# GRUBswitch_CustomHW_RevB.net
KiCad netlist of a schematic drawn in EAGLE
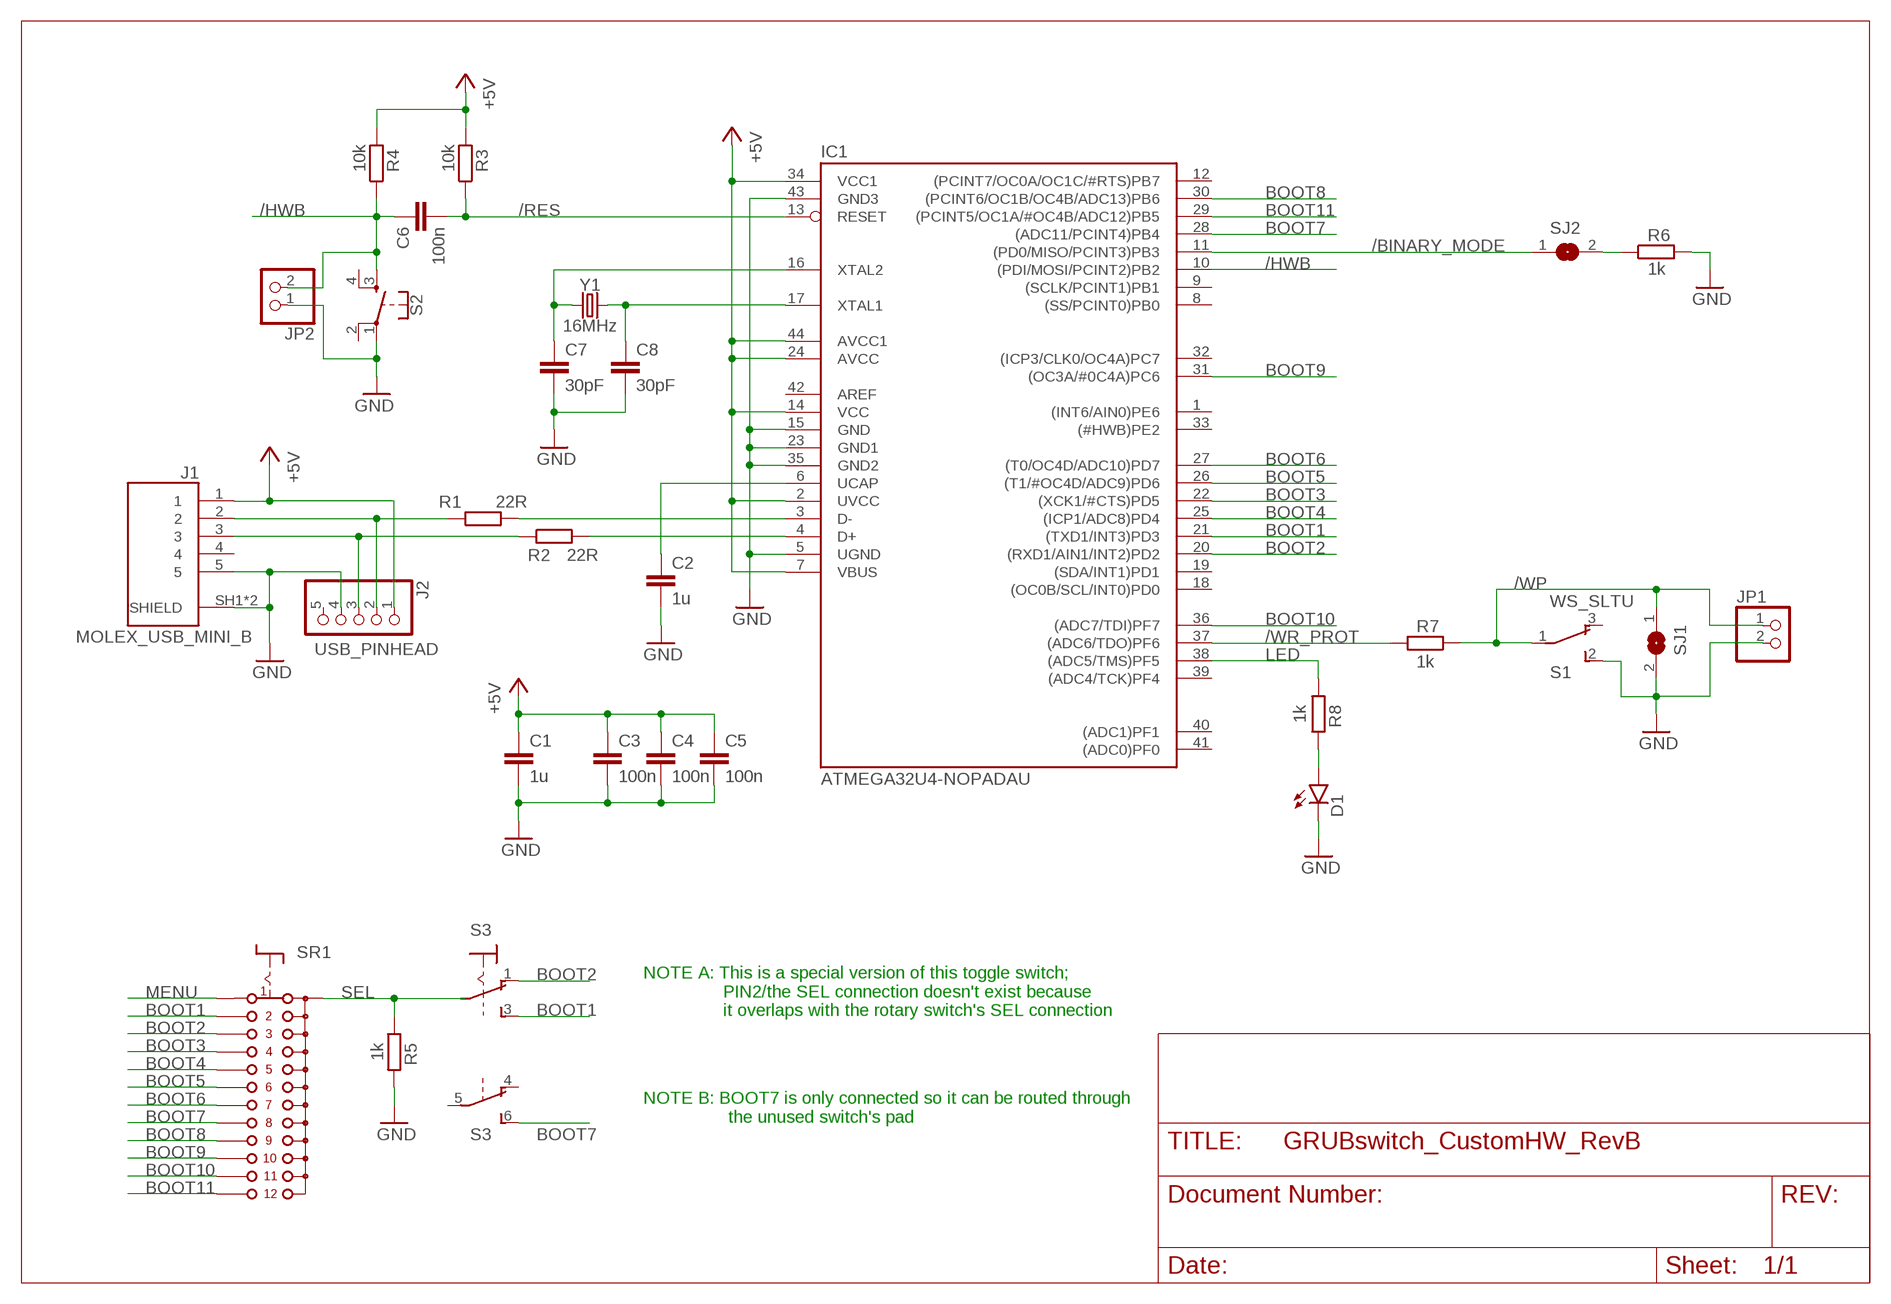
[diagram p0: schematic, sheet 1]

(export (version "E")
  (design (tool "Eeschema 10.0.6"))
  (components
    (comp (ref "C1")
      (value "1u")
      (footprint "eagle-import:C0805")
      (libsource (lib "eagle-import") (part "C-EUC0805"))
    )
    (comp (ref "C2")
      (value "1u")
      (footprint "eagle-import:C0805")
      (libsource (lib "eagle-import") (part "C-EUC0805"))
    )
    (comp (ref "C3")
      (value "100n")
      (footprint "eagle-import:C0805")
      (libsource (lib "eagle-import") (part "C-EUC0805"))
    )
    (comp (ref "C4")
      (value "100n")
      (footprint "eagle-import:C0805")
      (libsource (lib "eagle-import") (part "C-EUC0805"))
    )
    (comp (ref "C5")
      (value "100n")
      (footprint "eagle-import:C0805")
      (libsource (lib "eagle-import") (part "C-EUC0805"))
    )
    (comp (ref "C6")
      (value "100n")
      (footprint "eagle-import:C0805")
      (libsource (lib "eagle-import") (part "C-EUC0805"))
    )
    (comp (ref "C7")
      (value "30pF")
      (footprint "eagle-import:C0805")
      (libsource (lib "eagle-import") (part "C-EUC0805"))
    )
    (comp (ref "C8")
      (value "30pF")
      (footprint "eagle-import:C0805")
      (libsource (lib "eagle-import") (part "C-EUC0805"))
    )
    (comp (ref "D1")
      (value "LEDCHIPLED_0805")
      (footprint "eagle-import:CHIPLED_0805")
      (libsource (lib "eagle-import") (part "LEDCHIPLED_0805"))
    )
    (comp (ref "IC1")
      (value "ATMEGA32U4-NOPADAU")
      (footprint "eagle-import:TQFP44")
      (libsource (lib "eagle-import") (part "ATMEGA32U4-NOPADAU"))
    )
    (comp (ref "J1")
      (value "MOLEX_USB_MINI_B")
      (footprint "eagle-import:MOLEX_502237-0517")
      (libsource (lib "eagle-import") (part "MOLEX_USB_MINI_B"))
    )
    (comp (ref "J2")
      (value "USB_PINHEAD")
      (footprint "eagle-import:1X05")
      (libsource (lib "eagle-import") (part "PINHD-1X5"))
    )
    (comp (ref "JP1")
      (value "PINHD-1X2")
      (footprint "eagle-import:1X02")
      (libsource (lib "eagle-import") (part "PINHD-1X2"))
    )
    (comp (ref "JP2")
      (value "PINHD-1X2")
      (footprint "eagle-import:1X02")
      (libsource (lib "eagle-import") (part "PINHD-1X2"))
    )
    (comp (ref "R1")
      (value "22R")
      (footprint "eagle-import:R0805")
      (libsource (lib "eagle-import") (part "R-EU_R0805"))
    )
    (comp (ref "R2")
      (value "22R")
      (footprint "eagle-import:R0805")
      (libsource (lib "eagle-import") (part "R-EU_R0805"))
    )
    (comp (ref "R3")
      (value "10k")
      (footprint "eagle-import:R0805")
      (libsource (lib "eagle-import") (part "R-EU_R0805"))
    )
    (comp (ref "R4")
      (value "10k")
      (footprint "eagle-import:R0805")
      (libsource (lib "eagle-import") (part "R-EU_R0805"))
    )
    (comp (ref "R5")
      (value "1k")
      (footprint "eagle-import:R0805")
      (libsource (lib "eagle-import") (part "R-EU_R0805"))
    )
    (comp (ref "R6")
      (value "1k")
      (footprint "eagle-import:R0805")
      (libsource (lib "eagle-import") (part "R-EU_R0805"))
    )
    (comp (ref "R7")
      (value "1k")
      (footprint "eagle-import:R0805")
      (libsource (lib "eagle-import") (part "R-EU_R0805"))
    )
    (comp (ref "R8")
      (value "1k")
      (footprint "eagle-import:R0805")
      (libsource (lib "eagle-import") (part "R-EU_R0805"))
    )
    (comp (ref "S1")
      (value "WS_SLTU")
      (footprint "eagle-import:WS_SLTU")
      (libsource (lib "eagle-import") (part "WS_SLTU"))
    )
    (comp (ref "S2")
      (value "MOMENTARY-SWITCH-SPST-2-SMD-4.5MM")
      (footprint "eagle-import:TACTILE_SWITCH_SMD_4.5MM")
      (libsource (lib "eagle-import") (part "MOMENTARY-SWITCH-SPST-2-SMD-4.5MM"))
    )
    (comp (ref "S3")
      (value "M9040P2")
      (footprint "eagle-import:M9040P2")
      (libsource (lib "eagle-import") (part "M9040P2"))
    )
    (comp (ref "SJ1") (value "SJ") (footprint "eagle-import:SJ") (libsource (lib "eagle-import") (part "SJ")))
    (comp (ref "SJ2") (value "SJ") (footprint "eagle-import:SJ") (libsource (lib "eagle-import") (part "SJ")))
    (comp (ref "SR1")
      (value "CK101X12+")
      (footprint "eagle-import:CK101X12+")
      (libsource (lib "eagle-import") (part "CK101X12+"))
    )
    (comp (ref "Y1")
      (value "16MHz")
      (footprint "eagle-import:CRYSTAL-SMD-5X3.2-2PAD")
      (libsource (lib "eagle-import") (part "CRYSTALSMD-5X3.2-2PAD"))
    )
  )
  (nets
    (net (code "1") (name "+5V") (class "Default")
      (node (ref "C1") (pin "1") (pinfunction "1_1") (pintype "passive"))
      (node (ref "C3") (pin "1") (pinfunction "1_1") (pintype "passive"))
      (node (ref "C4") (pin "1") (pinfunction "1_1") (pintype "passive"))
      (node (ref "C5") (pin "1") (pinfunction "1_1") (pintype "passive"))
      (node (ref "IC1") (pin "14") (pinfunction "VCC_14") (pintype "power_in"))
      (node (ref "IC1") (pin "2") (pinfunction "UVCC_2") (pintype "power_in"))
      (node (ref "IC1") (pin "24") (pinfunction "AVCC_24") (pintype "power_in"))
      (node (ref "IC1") (pin "34") (pinfunction "VCC1_34") (pintype "power_in"))
      (node (ref "IC1") (pin "44") (pinfunction "AVCC1_44") (pintype "power_in"))
      (node (ref "IC1") (pin "7") (pinfunction "VBUS_7") (pintype "input"))
      (node (ref "J1") (pin "1") (pinfunction "1_1") (pintype "passive"))
      (node (ref "J2") (pin "1") (pinfunction "1_1") (pintype "passive"))
      (node (ref "R3") (pin "2") (pinfunction "2_2") (pintype "passive"))
      (node (ref "R4") (pin "2") (pinfunction "2_2") (pintype "passive"))
    )
    (net (code "2") (name "/AREF") (class "Default")
      (node (ref "IC1") (pin "42") (pinfunction "AREF_42") (pintype "power_in"))
    )
    (net (code "3") (name "/BOOT1") (class "Default")
      (node (ref "IC1") (pin "21") (pinfunction "(TXD1/INT3)PD3_21") (pintype "bidirectional"))
      (node (ref "S3") (pin "3") (pinfunction "S_3") (pintype "passive"))
      (node (ref "SR1") (pin "2") (pinfunction "2_2") (pintype "passive"))
    )
    (net (code "4") (name "/BOOT2") (class "Default")
      (node (ref "IC1") (pin "20") (pinfunction "(RXD1/AIN1/INT2)PD2_20") (pintype "bidirectional"))
      (node (ref "S3") (pin "1") (pinfunction "O_1") (pintype "passive"))
      (node (ref "SR1") (pin "3") (pinfunction "3_3") (pintype "passive"))
    )
    (net (code "5") (name "/BOOT3") (class "Default")
      (node (ref "IC1") (pin "22") (pinfunction "(XCK1/#CTS)PD5_22") (pintype "bidirectional"))
      (node (ref "SR1") (pin "4") (pinfunction "4_4") (pintype "passive"))
    )
    (net (code "6") (name "/BOOT4") (class "Default")
      (node (ref "IC1") (pin "25") (pinfunction "(ICP1/ADC8)PD4_25") (pintype "bidirectional"))
      (node (ref "SR1") (pin "5") (pinfunction "5_5") (pintype "passive"))
    )
    (net (code "7") (name "/BOOT5") (class "Default")
      (node (ref "IC1") (pin "26") (pinfunction "(T1/#OC4D/ADC9)PD6_26") (pintype "bidirectional"))
      (node (ref "SR1") (pin "6") (pinfunction "6_6") (pintype "passive"))
    )
    (net (code "8") (name "/BOOT6") (class "Default")
      (node (ref "IC1") (pin "27") (pinfunction "(T0/OC4D/ADC10)PD7_27") (pintype "bidirectional"))
      (node (ref "SR1") (pin "7") (pinfunction "7_7") (pintype "passive"))
    )
    (net (code "9") (name "/BOOT7") (class "Default")
      (node (ref "IC1") (pin "28") (pinfunction "(ADC11/PCINT4)PB4_28") (pintype "bidirectional"))
      (node (ref "S3") (pin "6") (pinfunction "S_6") (pintype "passive"))
      (node (ref "SR1") (pin "8") (pinfunction "8_8") (pintype "passive"))
    )
    (net (code "10") (name "/BOOT8") (class "Default")
      (node (ref "IC1") (pin "30") (pinfunction "(PCINT6/OC1B/OC4B/ADC13)PB6_30") (pintype "bidirectional"))
      (node (ref "SR1") (pin "9") (pinfunction "9_9") (pintype "passive"))
    )
    (net (code "11") (name "/BOOT9") (class "Default")
      (node (ref "IC1") (pin "31") (pinfunction "(OC3A/#0C4A)PC6_31") (pintype "bidirectional"))
      (node (ref "SR1") (pin "10") (pinfunction "10_10") (pintype "passive"))
    )
    (net (code "12") (name "/BOOT10") (class "Default")
      (node (ref "IC1") (pin "36") (pinfunction "(ADC7/TDI)PF7_36") (pintype "bidirectional"))
      (node (ref "SR1") (pin "11") (pinfunction "11_11") (pintype "passive"))
    )
    (net (code "13") (name "/BOOT11") (class "Default")
      (node (ref "IC1") (pin "29") (pinfunction "(PCINT5/OC1A/#OC4B/ADC12)PB5_29") (pintype "bidirectional"))
      (node (ref "SR1") (pin "12") (pinfunction "12_12") (pintype "passive"))
    )
    (net (code "14") (name "/LED") (class "Default")
      (node (ref "IC1") (pin "38") (pinfunction "(ADC5/TMS)PF5_38") (pintype "bidirectional"))
      (node (ref "R8") (pin "2") (pinfunction "2_2") (pintype "passive"))
    )
    (net (code "15") (name "/MENU") (class "Default")
      (node (ref "SR1") (pin "1") (pinfunction "1_1") (pintype "passive"))
    )
    (net (code "16") (name "/SEL") (class "Default")
      (node (ref "R5") (pin "1") (pinfunction "1_1") (pintype "passive"))
      (node (ref "SR1") (pin "A") (pinfunction "A_A") (pintype "passive"))
    )
    (net (code "17") (name "/{slash}BINARY_MODE") (class "Default")
      (node (ref "IC1") (pin "11") (pinfunction "(PD0/MISO/PCINT3)PB3_11") (pintype "bidirectional"))
      (node (ref "SJ2") (pin "1") (pinfunction "1_1") (pintype "passive"))
    )
    (net (code "18") (name "/{slash}HWB") (class "Default")
      (node (ref "C6") (pin "1") (pinfunction "1_1") (pintype "passive"))
      (node (ref "IC1") (pin "10") (pinfunction "(PDI/MOSI/PCINT2)PB2_10") (pintype "bidirectional"))
      (node (ref "JP2") (pin "2") (pinfunction "2_2") (pintype "passive"))
      (node (ref "R4") (pin "1") (pinfunction "1_1") (pintype "passive"))
      (node (ref "S2") (pin "3") (pinfunction "3_3") (pintype "passive"))
    )
    (net (code "19") (name "/{slash}RES") (class "Default")
      (node (ref "C6") (pin "2") (pinfunction "2_2") (pintype "passive"))
      (node (ref "IC1") (pin "13") (pinfunction "RESET_13") (pintype "input"))
      (node (ref "R3") (pin "1") (pinfunction "1_1") (pintype "passive"))
    )
    (net (code "20") (name "/{slash}WP") (class "Default")
      (node (ref "JP1") (pin "1") (pinfunction "1_1") (pintype "passive"))
      (node (ref "R7") (pin "1") (pinfunction "1_1") (pintype "passive"))
      (node (ref "S1") (pin "1") (pinfunction "P_1") (pintype "passive"))
      (node (ref "SJ1") (pin "1") (pinfunction "1_1") (pintype "passive"))
    )
    (net (code "21") (name "/{slash}WR_PROT") (class "Default")
      (node (ref "IC1") (pin "37") (pinfunction "(ADC6/TDO)PF6_37") (pintype "bidirectional"))
      (node (ref "R7") (pin "2") (pinfunction "2_2") (pintype "passive"))
    )
    (net (code "22") (name "GND") (class "Default")
      (node (ref "C1") (pin "2") (pinfunction "2_2") (pintype "passive"))
      (node (ref "C2") (pin "2") (pinfunction "2_2") (pintype "passive"))
      (node (ref "C3") (pin "2") (pinfunction "2_2") (pintype "passive"))
      (node (ref "C4") (pin "2") (pinfunction "2_2") (pintype "passive"))
      (node (ref "C5") (pin "2") (pinfunction "2_2") (pintype "passive"))
      (node (ref "C7") (pin "2") (pinfunction "2_2") (pintype "passive"))
      (node (ref "C8") (pin "2") (pinfunction "2_2") (pintype "passive"))
      (node (ref "D1") (pin "C") (pinfunction "C_C") (pintype "passive"))
      (node (ref "IC1") (pin "15") (pinfunction "GND_15") (pintype "power_in"))
      (node (ref "IC1") (pin "23") (pinfunction "GND1_23") (pintype "power_in"))
      (node (ref "IC1") (pin "35") (pinfunction "GND2_35") (pintype "power_in"))
      (node (ref "IC1") (pin "43") (pinfunction "GND3_43") (pintype "power_in"))
      (node (ref "IC1") (pin "5") (pinfunction "UGND_5") (pintype "power_in"))
      (node (ref "J1") (pin "5") (pinfunction "5_5") (pintype "passive"))
      (node (ref "J1") (pin "SH1") (pinfunction "SHIELD_SH1") (pintype "passive"))
      (node (ref "J1") (pin "SH2") (pinfunction "SHIELD_SH2") (pintype "passive"))
      (node (ref "J2") (pin "4") (pinfunction "4_4") (pintype "passive"))
      (node (ref "JP1") (pin "2") (pinfunction "2_2") (pintype "passive"))
      (node (ref "JP2") (pin "1") (pinfunction "1_1") (pintype "passive"))
      (node (ref "R5") (pin "2") (pinfunction "2_2") (pintype "passive"))
      (node (ref "R6") (pin "2") (pinfunction "2_2") (pintype "passive"))
      (node (ref "S1") (pin "2") (pinfunction "S_2") (pintype "passive"))
      (node (ref "S2") (pin "1") (pinfunction "1_1") (pintype "passive"))
      (node (ref "SJ1") (pin "2") (pinfunction "2_2") (pintype "passive"))
    )
    (net (code "23") (name "Net-(D1-PadA)") (class "Default")
      (node (ref "D1") (pin "A") (pinfunction "A_A") (pintype "passive"))
      (node (ref "R8") (pin "1") (pinfunction "1_1") (pintype "passive"))
    )
    (net (code "24") (name "Net-(IC1-D+)") (class "Default")
      (node (ref "IC1") (pin "4") (pinfunction "D+_4") (pintype "bidirectional"))
      (node (ref "R2") (pin "2") (pinfunction "2_2") (pintype "passive"))
    )
    (net (code "25") (name "Net-(IC1-D-)") (class "Default")
      (node (ref "IC1") (pin "3") (pinfunction "D-_3") (pintype "bidirectional"))
      (node (ref "R1") (pin "2") (pinfunction "2_2") (pintype "passive"))
    )
    (net (code "26") (name "Net-(IC1-UCAP)") (class "Default")
      (node (ref "C2") (pin "1") (pinfunction "1_1") (pintype "passive"))
      (node (ref "IC1") (pin "6") (pinfunction "UCAP_6") (pintype "passive"))
    )
    (net (code "27") (name "Net-(IC1-XTAL1)") (class "Default")
      (node (ref "C8") (pin "1") (pinfunction "1_1") (pintype "passive"))
      (node (ref "IC1") (pin "17") (pinfunction "XTAL1_17") (pintype "bidirectional"))
      (node (ref "Y1") (pin "P$2") (pinfunction "2_P$2") (pintype "passive"))
    )
    (net (code "28") (name "Net-(IC1-XTAL2)") (class "Default")
      (node (ref "C7") (pin "1") (pinfunction "1_1") (pintype "passive"))
      (node (ref "IC1") (pin "16") (pinfunction "XTAL2_16") (pintype "bidirectional"))
      (node (ref "Y1") (pin "P$1") (pinfunction "1_P$1") (pintype "passive"))
    )
    (net (code "29") (name "Net-(J1-Pad2)") (class "Default")
      (node (ref "J1") (pin "2") (pinfunction "2_2") (pintype "passive"))
      (node (ref "J2") (pin "2") (pinfunction "2_2") (pintype "passive"))
      (node (ref "R1") (pin "1") (pinfunction "1_1") (pintype "passive"))
    )
    (net (code "30") (name "Net-(J1-Pad3)") (class "Default")
      (node (ref "J1") (pin "3") (pinfunction "3_3") (pintype "passive"))
      (node (ref "J2") (pin "3") (pinfunction "3_3") (pintype "passive"))
      (node (ref "R2") (pin "1") (pinfunction "1_1") (pintype "passive"))
    )
    (net (code "31") (name "Net-(R6-Pad1)") (class "Default")
      (node (ref "R6") (pin "1") (pinfunction "1_1") (pintype "passive"))
      (node (ref "SJ2") (pin "2") (pinfunction "2_2") (pintype "passive"))
    )
    (net (code "32") (name "unconnected-(IC1-(#HWB)PE2-Pad33)") (class "Default")
      (node (ref "IC1") (pin "33") (pinfunction "(#HWB)PE2_33") (pintype "bidirectional"))
    )
    (net (code "33") (name "unconnected-(IC1-(ADC0)PF0-Pad41)") (class "Default")
      (node (ref "IC1") (pin "41") (pinfunction "(ADC0)PF0_41") (pintype "bidirectional"))
    )
    (net (code "34") (name "unconnected-(IC1-(ADC1)PF1-Pad40)") (class "Default")
      (node (ref "IC1") (pin "40") (pinfunction "(ADC1)PF1_40") (pintype "bidirectional"))
    )
    (net (code "35") (name "unconnected-(IC1-(ADC4{slash}TCK)PF4-Pad39)") (class "Default")
      (node (ref "IC1") (pin "39") (pinfunction "(ADC4/TCK)PF4_39") (pintype "bidirectional"))
    )
    (net (code "36") (name "unconnected-(IC1-(ICP3{slash}CLK0{slash}OC4A)PC7-Pad32)") (class "Default")
      (node (ref "IC1") (pin "32") (pinfunction "(ICP3/CLK0/OC4A)PC7_32") (pintype "bidirectional"))
    )
    (net (code "37") (name "unconnected-(IC1-(INT6{slash}AIN0)PE6-Pad1)") (class "Default")
      (node (ref "IC1") (pin "1") (pinfunction "(INT6/AIN0)PE6_1") (pintype "bidirectional"))
    )
    (net (code "38") (name "unconnected-(IC1-(OC0B{slash}SCL{slash}INT0)PD0-Pad18)") (class "Default")
      (node (ref "IC1") (pin "18") (pinfunction "(OC0B/SCL/INT0)PD0_18") (pintype "bidirectional"))
    )
    (net (code "39") (name "unconnected-(IC1-(PCINT7{slash}OC0A{slash}OC1C{slash}#RTS)PB7-Pad12)") (class "Default")
      (node (ref "IC1") (pin "12") (pinfunction "(PCINT7/OC0A/OC1C/#RTS)PB7_12") (pintype "bidirectional"))
    )
    (net (code "40") (name "unconnected-(IC1-(SCLK{slash}PCINT1)PB1-Pad9)") (class "Default")
      (node (ref "IC1") (pin "9") (pinfunction "(SCLK/PCINT1)PB1_9") (pintype "bidirectional"))
    )
    (net (code "41") (name "unconnected-(IC1-(SDA{slash}INT1)PD1-Pad19)") (class "Default")
      (node (ref "IC1") (pin "19") (pinfunction "(SDA/INT1)PD1_19") (pintype "bidirectional"))
    )
    (net (code "42") (name "unconnected-(IC1-(SS{slash}PCINT0)PB0-Pad8)") (class "Default")
      (node (ref "IC1") (pin "8") (pinfunction "(SS/PCINT0)PB0_8") (pintype "bidirectional"))
    )
    (net (code "43") (name "unconnected-(J1-Pad4)") (class "Default")
      (node (ref "J1") (pin "4") (pinfunction "4_4") (pintype "passive"))
    )
    (net (code "44") (name "unconnected-(J2-Pad5)") (class "Default")
      (node (ref "J2") (pin "5") (pinfunction "5_5") (pintype "passive"))
    )
    (net (code "45") (name "unconnected-(S1-O-Pad3)") (class "Default")
      (node (ref "S1") (pin "3") (pinfunction "O_3") (pintype "passive"))
    )
    (net (code "46") (name "unconnected-(S2-Pad2)") (class "Default")
      (node (ref "S2") (pin "2") (pinfunction "2_2") (pintype "passive"))
    )
    (net (code "47") (name "unconnected-(S2-Pad4)") (class "Default")
      (node (ref "S2") (pin "4") (pinfunction "4_4") (pintype "passive"))
    )
    (net (code "48") (name "unconnected-(S3B-O-Pad4)") (class "Default")
      (node (ref "S3") (pin "4") (pinfunction "O_4") (pintype "passive"))
    )
    (net (code "49") (name "unconnected-(S3B-P-Pad5)") (class "Default")
      (node (ref "S3") (pin "5") (pinfunction "P_5") (pintype "passive"))
    )
  )
)
